# Plasmarobo_canstop__canstop_2024-11-13.net
KiCad netlist of a schematic drawn in Altium Designer
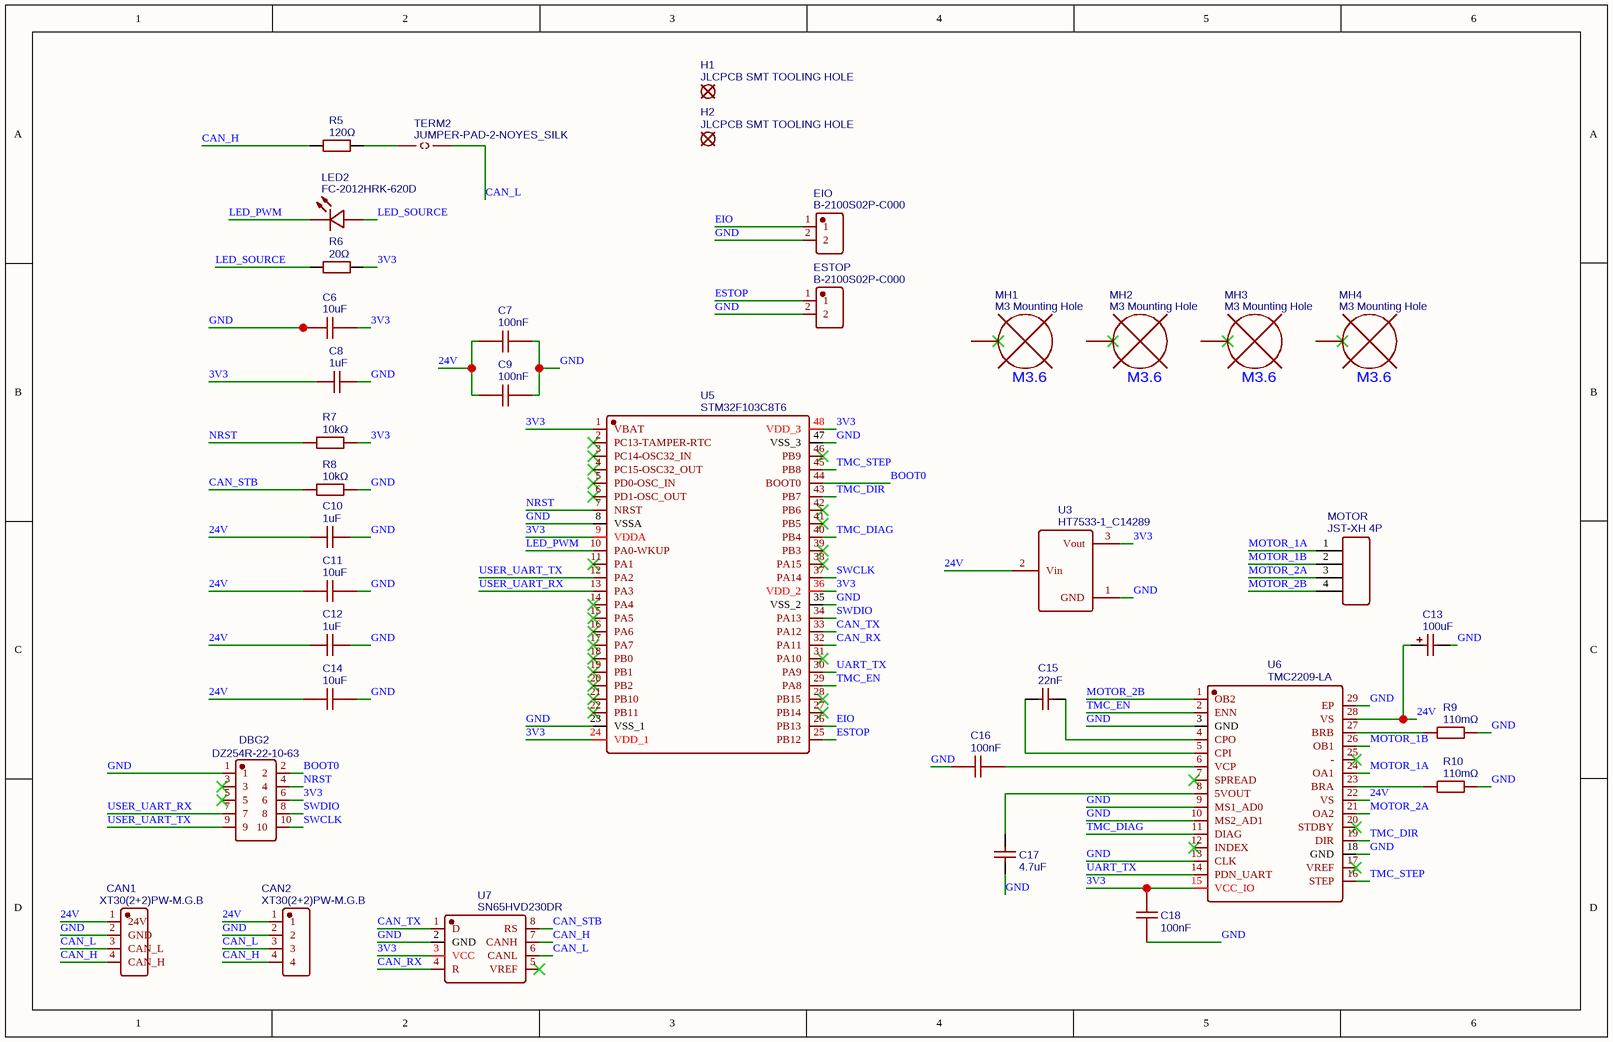
[diagram p0: Plasmarobo_canstop__canstop_2024-11-13.schdoc]

(export (version "E")
  (design (tool "Eeschema 10.0.6"))
  (components
    (comp (ref "C6")
      (value "10uF")
      (fields
        (field (name "MANUFACTURER PART") "CL21A106KAYNNNE")
        (field (name "MANUFACTURER") "SAMSUNG(三星)")
      )
      (libsource (lib "altium-import") (part "root_0_10uF_"))
    )
    (comp (ref "C7")
      (value "100nF")
      (fields
        (field (name "MANUFACTURER PART") "CC0805KRX7R9BB104")
        (field (name "MANUFACTURER") "YAGEO(国巨)")
      )
      (libsource (lib "altium-import") (part "root_0_100nF_"))
    )
    (comp (ref "C8")
      (value "1uF")
      (fields
        (field (name "MANUFACTURER PART") "CL21B105KBFNNNE")
        (field (name "MANUFACTURER") "SAMSUNG(三星)")
      )
      (libsource (lib "altium-import") (part "root_0_1uF_"))
    )
    (comp (ref "C9")
      (value "100nF")
      (fields
        (field (name "MANUFACTURER PART") "CC0805KRX7R9BB104")
        (field (name "MANUFACTURER") "YAGEO(国巨)")
      )
      (libsource (lib "altium-import") (part "root_0_100nF_"))
    )
    (comp (ref "C10")
      (value "1uF")
      (fields
        (field (name "MANUFACTURER PART") "CL21B105KBFNNNE")
        (field (name "MANUFACTURER") "SAMSUNG(三星)")
      )
      (libsource (lib "altium-import") (part "root_0_1uF_"))
    )
    (comp (ref "C11")
      (value "10uF")
      (fields
        (field (name "MANUFACTURER PART") "CL21A106KAYNNNE")
        (field (name "MANUFACTURER") "SAMSUNG(三星)")
      )
      (libsource (lib "altium-import") (part "root_0_10uF_"))
    )
    (comp (ref "C12")
      (value "1uF")
      (fields
        (field (name "MANUFACTURER PART") "CL21B105KBFNNNE")
        (field (name "MANUFACTURER") "SAMSUNG(三星)")
      )
      (libsource (lib "altium-import") (part "root_0_1uF_"))
    )
    (comp (ref "C13")
      (value "100uF")
      (fields
        (field (name "MANUFACTURER") "KEMET(基美)")
        (field (name "MANUFACTURER PART") "T491X107M025AT")
        (field (name "CONTRIBUTOR") "LCSC")
      )
      (libsource (lib "altium-import") (part "root_0_100uF_"))
    )
    (comp (ref "C14")
      (value "10uF")
      (fields
        (field (name "MANUFACTURER PART") "CL21A106KAYNNNE")
        (field (name "MANUFACTURER") "SAMSUNG(三星)")
      )
      (libsource (lib "altium-import") (part "root_0_10uF_"))
    )
    (comp (ref "C15")
      (value "22nF")
      (fields
        (field (name "MANUFACTURER PART") "CL10B223KB8NNNC")
        (field (name "MANUFACTURER") "SAMSUNG(三星)")
      )
      (libsource (lib "altium-import") (part "root_0_22nF_"))
    )
    (comp (ref "C16")
      (value "100nF")
      (fields
        (field (name "MANUFACTURER") "YAGEO(国巨)")
        (field (name "MANUFACTURER PART") "CC0603KRX7R9BB104")
      )
      (libsource (lib "altium-import") (part "root_0_100nF_"))
    )
    (comp (ref "C17")
      (value "4.7uF")
      (fields
        (field (name "MANUFACTURER PART") "CL10A475KO8NNNC")
        (field (name "MANUFACTURER") "SAMSUNG(三星)")
      )
      (libsource (lib "altium-import") (part "root_1_4.7uF_"))
    )
    (comp (ref "C18")
      (value "100nF")
      (fields
        (field (name "MANUFACTURER") "YAGEO(国巨)")
        (field (name "MANUFACTURER PART") "CC0603KRX7R9BB104")
      )
      (libsource (lib "altium-import") (part "root_1_100nF_"))
    )
    (comp (ref "CAN1")
      (value "XT30(2+2)PW-M.G.B")
      (fields (field (name "MANUFACTURER") "AMASS(艾迈斯)") (field (name "CONTRIBUTOR") "chathamja"))
      (libsource (lib "altium-import") (part "root_3_XT30(2+2)PW-M.G.B_"))
    )
    (comp (ref "CAN2")
      (value "XT30(2+2)PW-M.G.B")
      (fields (field (name "MANUFACTURER") "AMASS(艾迈斯)") (field (name "CONTRIBUTOR") "chathamja"))
      (libsource (lib "altium-import") (part "root_3_XT30(2+2)PW-M.G.B_"))
    )
    (comp (ref "DBG2")
      (value "DZ254R-22-10-63")
      (fields (field (name "MANUFACTURER") "DEALON(德艺隆)") (field (name "CONTRIBUTOR") "LCSC"))
      (libsource (lib "altium-import") (part "root_0_DZ254R-22-10-63_"))
    )
    (comp (ref "EIO")
      (value "B-2100S02P-C000")
      (fields (field (name "MANUFACTURER") "Ckmtw(灿科盟)") (field (name "CONTRIBUTOR") "LCSC"))
      (libsource (lib "altium-import") (part "root_0_B-2100S02P-C000_"))
    )
    (comp (ref "ESTOP")
      (value "B-2100S02P-C000")
      (fields (field (name "MANUFACTURER") "Ckmtw(灿科盟)") (field (name "CONTRIBUTOR") "LCSC"))
      (libsource (lib "altium-import") (part "root_0_B-2100S02P-C000_"))
    )
    (comp (ref "H1")
      (value "JLCPCB SMT TOOLING HOLE")
      (fields (field (name "CONTRIBUTOR") "Sindel90"))
      (libsource (lib "altium-import") (part "root_0_JLCPCB SMT TOOLING HOLE_"))
    )
    (comp (ref "H2")
      (value "JLCPCB SMT TOOLING HOLE")
      (fields (field (name "CONTRIBUTOR") "Sindel90"))
      (libsource (lib "altium-import") (part "root_0_JLCPCB SMT TOOLING HOLE_"))
    )
    (comp (ref "LED2")
      (value "FC-2012HRK-620D")
      (fields (field (name "MANUFACTURER") "国星光电") (field (name "MANUFACTURER PART") "NCD0805R1"))
      (libsource (lib "altium-import") (part "root_0_FC-2012HRK-620D_"))
    )
    (comp (ref "MH1")
      (value "M3 Mounting Hole")
      (fields (field (name "CONTRIBUTOR") "StefMas"))
      (libsource (lib "altium-import") (part "root_0_M3 Mounting Hole_"))
    )
    (comp (ref "MH2")
      (value "M3 Mounting Hole")
      (fields (field (name "CONTRIBUTOR") "StefMas"))
      (libsource (lib "altium-import") (part "root_0_M3 Mounting Hole_"))
    )
    (comp (ref "MH3")
      (value "M3 Mounting Hole")
      (fields (field (name "CONTRIBUTOR") "StefMas"))
      (libsource (lib "altium-import") (part "root_0_M3 Mounting Hole_"))
    )
    (comp (ref "MH4")
      (value "M3 Mounting Hole")
      (fields (field (name "CONTRIBUTOR") "StefMas"))
      (libsource (lib "altium-import") (part "root_0_M3 Mounting Hole_"))
    )
    (comp (ref "MOTOR")
      (value "JST-XH 4P")
      (fields (field (name "CONTRIBUTOR") "ordialesjeremiah"))
      (libsource (lib "altium-import") (part "root_0_JST-XH 4P_"))
    )
    (comp (ref "R5")
      (value "120Ω")
      (fields
        (field (name "MANUFACTURER") "UNI-ROYAL(厚声)")
        (field (name "MANUFACTURER PART") "0805W8F1200T5E")
      )
      (libsource (lib "altium-import") (part "root_0_120Ω_"))
    )
    (comp (ref "R6")
      (value "20Ω")
      (fields
        (field (name "MANUFACTURER") "UNI-ROYAL(厚声)")
        (field (name "MANUFACTURER PART") "0805W8F200JT5E")
      )
      (libsource (lib "altium-import") (part "root_0_20Ω_"))
    )
    (comp (ref "R7")
      (value "10kΩ")
      (fields
        (field (name "MANUFACTURER") "UNI-ROYAL(厚声)")
        (field (name "MANUFACTURER PART") "0805W8F1002T5E")
      )
      (libsource (lib "altium-import") (part "root_0_10kΩ_"))
    )
    (comp (ref "R8")
      (value "10kΩ")
      (fields
        (field (name "MANUFACTURER") "UNI-ROYAL(厚声)")
        (field (name "MANUFACTURER PART") "0805W8F1002T5E")
      )
      (libsource (lib "altium-import") (part "root_0_10kΩ_"))
    )
    (comp (ref "R9")
      (value "110mΩ")
      (fields
        (field (name "MANUFACTURER") "RALEC(旺诠)")
        (field (name "MANUFACTURER PART") "RTT12R110FTP")
        (field (name "CONTRIBUTOR") "LCSC")
      )
      (libsource (lib "altium-import") (part "root_0_110mΩ_"))
    )
    (comp (ref "R10")
      (value "110mΩ")
      (fields
        (field (name "MANUFACTURER") "RALEC(旺诠)")
        (field (name "MANUFACTURER PART") "RTT12R110FTP")
        (field (name "CONTRIBUTOR") "LCSC")
      )
      (libsource (lib "altium-import") (part "root_0_110mΩ_"))
    )
    (comp (ref "TERM2")
      (value "JUMPER-PAD-2-NOYES_SILK")
      (fields (field (name "CONTRIBUTOR") "SparkFun"))
      (libsource (lib "altium-import") (part "root_0_JUMPER-PAD-2-NOYES_SILK_"))
    )
    (comp (ref "U3")
      (value "HT7533-1_C14289")
      (fields (field (name "MANUFACTURER") "HOLTEK(合泰/盛群)") (field (name "MANUFACTURER PART") "HT7533-1"))
      (libsource (lib "altium-import") (part "root_0_HT7533-1_C14289_"))
    )
    (comp (ref "U5")
      (value "STM32F103C8T6")
      (fields (field (name "MANUFACTURER") "ST(意法半导体)"))
      (libsource (lib "altium-import") (part "root_0_STM32F103C8T6_"))
    )
    (comp (ref "U6")
      (value "TMC2209-LA")
      (fields (field (name "MANUFACTURER") "TRINAMIC") (field (name "CONTRIBUTOR") "LCSC"))
      (libsource (lib "altium-import") (part "root_0_TMC2209-LA_"))
    )
    (comp (ref "U7")
      (value "SN65HVD230DR")
      (fields (field (name "MANUFACTURER") "TI(德州仪器)"))
      (libsource (lib "altium-import") (part "root_0_SN65HVD230DR_"))
    )
  )
  (nets
    (net (code "1") (name "/3V3") (class "Default")
      (node (ref "C18") (pin "2") (pinfunction "2_2") (pintype "passive"))
      (node (ref "C6") (pin "2") (pinfunction "2_2") (pintype "passive"))
      (node (ref "C8") (pin "1") (pinfunction "1_1") (pintype "passive"))
      (node (ref "DBG2") (pin "6") (pinfunction "6_6") (pintype "passive"))
      (node (ref "R6") (pin "2") (pinfunction "2_2") (pintype "passive"))
      (node (ref "R7") (pin "2") (pinfunction "2_2") (pintype "passive"))
      (node (ref "U3") (pin "3") (pinfunction "Vout_3") (pintype "passive"))
      (node (ref "U5") (pin "1") (pinfunction "VBAT_1") (pintype "passive"))
      (node (ref "U5") (pin "24") (pinfunction "VDD_1_24") (pintype "passive"))
      (node (ref "U5") (pin "36") (pinfunction "VDD_2_36") (pintype "passive"))
      (node (ref "U5") (pin "48") (pinfunction "VDD_3_48") (pintype "passive"))
      (node (ref "U5") (pin "9") (pinfunction "VDDA_9") (pintype "passive"))
      (node (ref "U6") (pin "15") (pinfunction "VCC_IO_15") (pintype "passive"))
      (node (ref "U7") (pin "3") (pinfunction "VCC_3") (pintype "passive"))
    )
    (net (code "2") (name "/24V") (class "Default")
      (node (ref "C10") (pin "1") (pinfunction "1_1") (pintype "passive"))
      (node (ref "C11") (pin "1") (pinfunction "1_1") (pintype "passive"))
      (node (ref "C12") (pin "1") (pinfunction "1_1") (pintype "passive"))
      (node (ref "C13") (pin "1") (pinfunction "1_1") (pintype "passive"))
      (node (ref "C14") (pin "1") (pinfunction "1_1") (pintype "passive"))
      (node (ref "C7") (pin "1") (pinfunction "1_1") (pintype "passive"))
      (node (ref "C9") (pin "1") (pinfunction "1_1") (pintype "passive"))
      (node (ref "CAN1") (pin "1") (pinfunction "24V_1") (pintype "passive"))
      (node (ref "CAN2") (pin "1") (pinfunction "24V_1") (pintype "passive"))
      (node (ref "U3") (pin "2") (pinfunction "Vin_2") (pintype "passive"))
      (node (ref "U6") (pin "22") (pinfunction "VS_22") (pintype "passive"))
      (node (ref "U6") (pin "28") (pinfunction "VS_28") (pintype "passive"))
    )
    (net (code "3") (name "/BOOT0") (class "Default")
      (node (ref "DBG2") (pin "2") (pinfunction "2_2") (pintype "passive"))
      (node (ref "U5") (pin "44") (pinfunction "BOOT0_44") (pintype "passive"))
    )
    (net (code "4") (name "/CAN_H") (class "Default")
      (node (ref "CAN1") (pin "4") (pinfunction "CAN_H_4") (pintype "passive"))
      (node (ref "CAN2") (pin "4") (pinfunction "CAN_H_4") (pintype "passive"))
      (node (ref "R5") (pin "1") (pinfunction "1_1") (pintype "passive"))
      (node (ref "U7") (pin "7") (pinfunction "CANH_7") (pintype "passive"))
    )
    (net (code "5") (name "/CAN_L") (class "Default")
      (node (ref "CAN1") (pin "3") (pinfunction "CAN_L_3") (pintype "passive"))
      (node (ref "CAN2") (pin "3") (pinfunction "CAN_L_3") (pintype "passive"))
      (node (ref "TERM2") (pin "2") (pinfunction "2_2") (pintype "passive"))
      (node (ref "U7") (pin "6") (pinfunction "CANL_6") (pintype "passive"))
    )
    (net (code "6") (name "/CAN_RX") (class "Default")
      (node (ref "U5") (pin "32") (pinfunction "PA11_32") (pintype "passive"))
      (node (ref "U7") (pin "4") (pinfunction "R_4") (pintype "passive"))
    )
    (net (code "7") (name "/CAN_STB") (class "Default")
      (node (ref "R8") (pin "1") (pinfunction "1_1") (pintype "passive"))
      (node (ref "U7") (pin "8") (pinfunction "RS_8") (pintype "passive"))
    )
    (net (code "8") (name "/CAN_TX") (class "Default")
      (node (ref "U5") (pin "33") (pinfunction "PA12_33") (pintype "passive"))
      (node (ref "U7") (pin "1") (pinfunction "D_1") (pintype "passive"))
    )
    (net (code "9") (name "/EIO") (class "Default")
      (node (ref "EIO") (pin "1") (pinfunction "1_1") (pintype "passive"))
      (node (ref "U5") (pin "26") (pinfunction "PB13_26") (pintype "passive"))
    )
    (net (code "10") (name "/ESTOP") (class "Default")
      (node (ref "ESTOP") (pin "1") (pinfunction "1_1") (pintype "passive"))
      (node (ref "U5") (pin "25") (pinfunction "PB12_25") (pintype "passive"))
    )
    (net (code "11") (name "/GND") (class "Default")
      (node (ref "C10") (pin "2") (pinfunction "2_2") (pintype "passive"))
      (node (ref "C11") (pin "2") (pinfunction "2_2") (pintype "passive"))
      (node (ref "C12") (pin "2") (pinfunction "2_2") (pintype "passive"))
      (node (ref "C13") (pin "2") (pinfunction "2_2") (pintype "passive"))
      (node (ref "C14") (pin "2") (pinfunction "2_2") (pintype "passive"))
      (node (ref "C16") (pin "1") (pinfunction "1_1") (pintype "passive"))
      (node (ref "C17") (pin "1") (pinfunction "1_1") (pintype "passive"))
      (node (ref "C18") (pin "1") (pinfunction "1_1") (pintype "passive"))
      (node (ref "C6") (pin "1") (pinfunction "1_1") (pintype "passive"))
      (node (ref "C7") (pin "2") (pinfunction "2_2") (pintype "passive"))
      (node (ref "C8") (pin "2") (pinfunction "2_2") (pintype "passive"))
      (node (ref "C9") (pin "2") (pinfunction "2_2") (pintype "passive"))
      (node (ref "CAN1") (pin "2") (pinfunction "GND_2") (pintype "passive"))
      (node (ref "CAN2") (pin "2") (pinfunction "GND_2") (pintype "passive"))
      (node (ref "DBG2") (pin "1") (pinfunction "1_1") (pintype "passive"))
      (node (ref "EIO") (pin "2") (pinfunction "2_2") (pintype "passive"))
      (node (ref "ESTOP") (pin "2") (pinfunction "2_2") (pintype "passive"))
      (node (ref "R10") (pin "2") (pinfunction "2_2") (pintype "passive"))
      (node (ref "R8") (pin "2") (pinfunction "2_2") (pintype "passive"))
      (node (ref "R9") (pin "2") (pinfunction "2_2") (pintype "passive"))
      (node (ref "U3") (pin "1") (pinfunction "GND_1") (pintype "passive"))
      (node (ref "U5") (pin "23") (pinfunction "VSS_1_23") (pintype "passive"))
      (node (ref "U5") (pin "35") (pinfunction "VSS_2_35") (pintype "passive"))
      (node (ref "U5") (pin "47") (pinfunction "VSS_3_47") (pintype "passive"))
      (node (ref "U5") (pin "8") (pinfunction "VSSA_8") (pintype "passive"))
      (node (ref "U6") (pin "10") (pinfunction "MS2_AD1_10") (pintype "passive"))
      (node (ref "U6") (pin "13") (pinfunction "CLK_13") (pintype "passive"))
      (node (ref "U6") (pin "18") (pinfunction "GND_18") (pintype "passive"))
      (node (ref "U6") (pin "29") (pinfunction "EP_29") (pintype "passive"))
      (node (ref "U6") (pin "3") (pinfunction "GND_3") (pintype "passive"))
      (node (ref "U6") (pin "9") (pinfunction "MS1_AD0_9") (pintype "passive"))
      (node (ref "U7") (pin "2") (pinfunction "GND_2") (pintype "passive"))
    )
    (net (code "12") (name "/LED_PWM") (class "Default")
      (node (ref "LED2") (pin "2") (pinfunction "-_2") (pintype "passive"))
      (node (ref "U5") (pin "10") (pinfunction "PA0-WKUP_10") (pintype "passive"))
    )
    (net (code "13") (name "/LED_SOURCE") (class "Default")
      (node (ref "LED2") (pin "1") (pinfunction "+_1") (pintype "passive"))
      (node (ref "R6") (pin "1") (pinfunction "1_1") (pintype "passive"))
    )
    (net (code "14") (name "/MOTOR_1A") (class "Default")
      (node (ref "MOTOR") (pin "1") (pinfunction "1_1") (pintype "passive"))
      (node (ref "U6") (pin "24") (pinfunction "OA1_24") (pintype "passive"))
    )
    (net (code "15") (name "/MOTOR_1B") (class "Default")
      (node (ref "MOTOR") (pin "2") (pinfunction "2_2") (pintype "passive"))
      (node (ref "U6") (pin "26") (pinfunction "OB1_26") (pintype "passive"))
    )
    (net (code "16") (name "/MOTOR_2A") (class "Default")
      (node (ref "MOTOR") (pin "3") (pinfunction "3_3") (pintype "passive"))
      (node (ref "U6") (pin "21") (pinfunction "OA2_21") (pintype "passive"))
    )
    (net (code "17") (name "/MOTOR_2B") (class "Default")
      (node (ref "MOTOR") (pin "4") (pinfunction "4_4") (pintype "passive"))
      (node (ref "U6") (pin "1") (pinfunction "OB2_1") (pintype "passive"))
    )
    (net (code "18") (name "/NRST") (class "Default")
      (node (ref "DBG2") (pin "4") (pinfunction "4_4") (pintype "passive"))
      (node (ref "R7") (pin "1") (pinfunction "1_1") (pintype "passive"))
      (node (ref "U5") (pin "7") (pinfunction "NRST_7") (pintype "passive"))
    )
    (net (code "19") (name "/SWCLK") (class "Default")
      (node (ref "DBG2") (pin "10") (pinfunction "10_10") (pintype "passive"))
      (node (ref "U5") (pin "37") (pinfunction "PA14_37") (pintype "passive"))
    )
    (net (code "20") (name "/SWDIO") (class "Default")
      (node (ref "DBG2") (pin "8") (pinfunction "8_8") (pintype "passive"))
      (node (ref "U5") (pin "34") (pinfunction "PA13_34") (pintype "passive"))
    )
    (net (code "21") (name "/TMC_DIAG") (class "Default")
      (node (ref "U5") (pin "40") (pinfunction "PB4_40") (pintype "passive"))
      (node (ref "U6") (pin "11") (pinfunction "DIAG_11") (pintype "passive"))
    )
    (net (code "22") (name "/TMC_DIR") (class "Default")
      (node (ref "U5") (pin "43") (pinfunction "PB7_43") (pintype "passive"))
      (node (ref "U6") (pin "19") (pinfunction "DIR_19") (pintype "passive"))
    )
    (net (code "23") (name "/TMC_EN") (class "Default")
      (node (ref "U5") (pin "29") (pinfunction "PA8_29") (pintype "passive"))
      (node (ref "U6") (pin "2") (pinfunction "ENN_2") (pintype "passive"))
    )
    (net (code "24") (name "/TMC_STEP") (class "Default")
      (node (ref "U5") (pin "45") (pinfunction "PB8_45") (pintype "passive"))
      (node (ref "U6") (pin "16") (pinfunction "STEP_16") (pintype "passive"))
    )
    (net (code "25") (name "/UART_TX") (class "Default")
      (node (ref "U5") (pin "30") (pinfunction "PA9_30") (pintype "passive"))
      (node (ref "U6") (pin "14") (pinfunction "PDN_UART_14") (pintype "passive"))
    )
    (net (code "26") (name "/USER_UART_RX") (class "Default")
      (node (ref "DBG2") (pin "7") (pinfunction "7_7") (pintype "passive"))
      (node (ref "U5") (pin "13") (pinfunction "PA3_13") (pintype "passive"))
    )
    (net (code "27") (name "/USER_UART_TX") (class "Default")
      (node (ref "DBG2") (pin "9") (pinfunction "9_9") (pintype "passive"))
      (node (ref "U5") (pin "12") (pinfunction "PA2_12") (pintype "passive"))
    )
    (net (code "28") (name "Net-(R5-Pad2)") (class "Default")
      (node (ref "R5") (pin "2") (pinfunction "2_2") (pintype "passive"))
      (node (ref "TERM2") (pin "1") (pinfunction "1_1") (pintype "passive"))
    )
    (net (code "29") (name "Net-(U6-5VOUT)") (class "Default")
      (node (ref "C17") (pin "2") (pinfunction "2_2") (pintype "passive"))
      (node (ref "U6") (pin "8") (pinfunction "5VOUT_8") (pintype "passive"))
    )
    (net (code "30") (name "Net-(U6-BRA)") (class "Default")
      (node (ref "R10") (pin "1") (pinfunction "1_1") (pintype "passive"))
      (node (ref "U6") (pin "23") (pinfunction "BRA_23") (pintype "passive"))
    )
    (net (code "31") (name "Net-(U6-BRB)") (class "Default")
      (node (ref "R9") (pin "1") (pinfunction "1_1") (pintype "passive"))
      (node (ref "U6") (pin "27") (pinfunction "BRB_27") (pintype "passive"))
    )
    (net (code "32") (name "Net-(U6-CPI)") (class "Default")
      (node (ref "C15") (pin "1") (pinfunction "1_1") (pintype "passive"))
      (node (ref "U6") (pin "5") (pinfunction "CPI_5") (pintype "passive"))
    )
    (net (code "33") (name "Net-(U6-CPO)") (class "Default")
      (node (ref "C15") (pin "2") (pinfunction "2_2") (pintype "passive"))
      (node (ref "U6") (pin "4") (pinfunction "CPO_4") (pintype "passive"))
    )
    (net (code "34") (name "Net-(U6-VCP)") (class "Default")
      (node (ref "C16") (pin "2") (pinfunction "2_2") (pintype "passive"))
      (node (ref "U6") (pin "6") (pinfunction "VCP_6") (pintype "passive"))
    )
    (net (code "35") (name "unconnected-(DBG2-Pad3)") (class "Default")
      (node (ref "DBG2") (pin "3") (pinfunction "3_3") (pintype "passive+no_connect"))
    )
    (net (code "36") (name "unconnected-(DBG2-Pad5)") (class "Default")
      (node (ref "DBG2") (pin "5") (pinfunction "5_5") (pintype "passive+no_connect"))
    )
    (net (code "37") (name "unconnected-(MH1-Pad1)") (class "Default")
      (node (ref "MH1") (pin "1") (pinfunction "1_1") (pintype "passive+no_connect"))
    )
    (net (code "38") (name "unconnected-(MH2-Pad1)") (class "Default")
      (node (ref "MH2") (pin "1") (pinfunction "1_1") (pintype "passive+no_connect"))
    )
    (net (code "39") (name "unconnected-(MH3-Pad1)") (class "Default")
      (node (ref "MH3") (pin "1") (pinfunction "1_1") (pintype "passive+no_connect"))
    )
    (net (code "40") (name "unconnected-(MH4-Pad1)") (class "Default")
      (node (ref "MH4") (pin "1") (pinfunction "1_1") (pintype "passive+no_connect"))
    )
    (net (code "41") (name "unconnected-(U5-PA1-Pad11)") (class "Default")
      (node (ref "U5") (pin "11") (pinfunction "PA1_11") (pintype "passive+no_connect"))
    )
    (net (code "42") (name "unconnected-(U5-PA4-Pad14)") (class "Default")
      (node (ref "U5") (pin "14") (pinfunction "PA4_14") (pintype "passive+no_connect"))
    )
    (net (code "43") (name "unconnected-(U5-PA5-Pad15)") (class "Default")
      (node (ref "U5") (pin "15") (pinfunction "PA5_15") (pintype "passive+no_connect"))
    )
    (net (code "44") (name "unconnected-(U5-PA6-Pad16)") (class "Default")
      (node (ref "U5") (pin "16") (pinfunction "PA6_16") (pintype "passive+no_connect"))
    )
    (net (code "45") (name "unconnected-(U5-PA7-Pad17)") (class "Default")
      (node (ref "U5") (pin "17") (pinfunction "PA7_17") (pintype "passive+no_connect"))
    )
    (net (code "46") (name "unconnected-(U5-PA10-Pad31)") (class "Default")
      (node (ref "U5") (pin "31") (pinfunction "PA10_31") (pintype "passive+no_connect"))
    )
    (net (code "47") (name "unconnected-(U5-PA15-Pad38)") (class "Default")
      (node (ref "U5") (pin "38") (pinfunction "PA15_38") (pintype "passive+no_connect"))
    )
    (net (code "48") (name "unconnected-(U5-PB0-Pad18)") (class "Default")
      (node (ref "U5") (pin "18") (pinfunction "PB0_18") (pintype "passive+no_connect"))
    )
    (net (code "49") (name "unconnected-(U5-PB1-Pad19)") (class "Default")
      (node (ref "U5") (pin "19") (pinfunction "PB1_19") (pintype "passive+no_connect"))
    )
    (net (code "50") (name "unconnected-(U5-PB2-Pad20)") (class "Default")
      (node (ref "U5") (pin "20") (pinfunction "PB2_20") (pintype "passive+no_connect"))
    )
    (net (code "51") (name "unconnected-(U5-PB3-Pad39)") (class "Default")
      (node (ref "U5") (pin "39") (pinfunction "PB3_39") (pintype "passive+no_connect"))
    )
    (net (code "52") (name "unconnected-(U5-PB5-Pad41)") (class "Default")
      (node (ref "U5") (pin "41") (pinfunction "PB5_41") (pintype "passive+no_connect"))
    )
    (net (code "53") (name "unconnected-(U5-PB6-Pad42)") (class "Default")
      (node (ref "U5") (pin "42") (pinfunction "PB6_42") (pintype "passive+no_connect"))
    )
    (net (code "54") (name "unconnected-(U5-PB9-Pad46)") (class "Default")
      (node (ref "U5") (pin "46") (pinfunction "PB9_46") (pintype "passive+no_connect"))
    )
    (net (code "55") (name "unconnected-(U5-PB10-Pad21)") (class "Default")
      (node (ref "U5") (pin "21") (pinfunction "PB10_21") (pintype "passive+no_connect"))
    )
    (net (code "56") (name "unconnected-(U5-PB11-Pad22)") (class "Default")
      (node (ref "U5") (pin "22") (pinfunction "PB11_22") (pintype "passive+no_connect"))
    )
    (net (code "57") (name "unconnected-(U5-PB14-Pad27)") (class "Default")
      (node (ref "U5") (pin "27") (pinfunction "PB14_27") (pintype "passive+no_connect"))
    )
    (net (code "58") (name "unconnected-(U5-PB15-Pad28)") (class "Default")
      (node (ref "U5") (pin "28") (pinfunction "PB15_28") (pintype "passive+no_connect"))
    )
    (net (code "59") (name "unconnected-(U5-PC13-TAMPER-RTC-Pad2)") (class "Default")
      (node (ref "U5") (pin "2") (pinfunction "PC13-TAMPER-RTC_2") (pintype "passive+no_connect"))
    )
    (net (code "60") (name "unconnected-(U5-PC14-OSC32_IN-Pad3)") (class "Default")
      (node (ref "U5") (pin "3") (pinfunction "PC14-OSC32_IN_3") (pintype "passive+no_connect"))
    )
    (net (code "61") (name "unconnected-(U5-PC15-OSC32_OUT-Pad4)") (class "Default")
      (node (ref "U5") (pin "4") (pinfunction "PC15-OSC32_OUT_4") (pintype "passive+no_connect"))
    )
    (net (code "62") (name "unconnected-(U5-PD0-OSC_IN-Pad5)") (class "Default")
      (node (ref "U5") (pin "5") (pinfunction "PD0-OSC_IN_5") (pintype "passive+no_connect"))
    )
    (net (code "63") (name "unconnected-(U5-PD1-OSC_OUT-Pad6)") (class "Default")
      (node (ref "U5") (pin "6") (pinfunction "PD1-OSC_OUT_6") (pintype "passive+no_connect"))
    )
    (net (code "64") (name "unconnected-(U6---Pad25)") (class "Default")
      (node (ref "U6") (pin "25") (pinfunction "-_25") (pintype "passive+no_connect"))
    )
    (net (code "65") (name "unconnected-(U6-INDEX-Pad12)") (class "Default")
      (node (ref "U6") (pin "12") (pinfunction "INDEX_12") (pintype "passive+no_connect"))
    )
    (net (code "66") (name "unconnected-(U6-SPREAD-Pad7)") (class "Default")
      (node (ref "U6") (pin "7") (pinfunction "SPREAD_7") (pintype "passive+no_connect"))
    )
    (net (code "67") (name "unconnected-(U6-STDBY-Pad20)") (class "Default")
      (node (ref "U6") (pin "20") (pinfunction "STDBY_20") (pintype "passive+no_connect"))
    )
    (net (code "68") (name "unconnected-(U6-VREF-Pad17)") (class "Default")
      (node (ref "U6") (pin "17") (pinfunction "VREF_17") (pintype "passive+no_connect"))
    )
    (net (code "69") (name "unconnected-(U7-VREF-Pad5)") (class "Default")
      (node (ref "U7") (pin "5") (pinfunction "VREF_5") (pintype "passive+no_connect"))
    )
  )
)
